# 00_power.net
KiCad netlist of a schematic drawn in Altium Designer
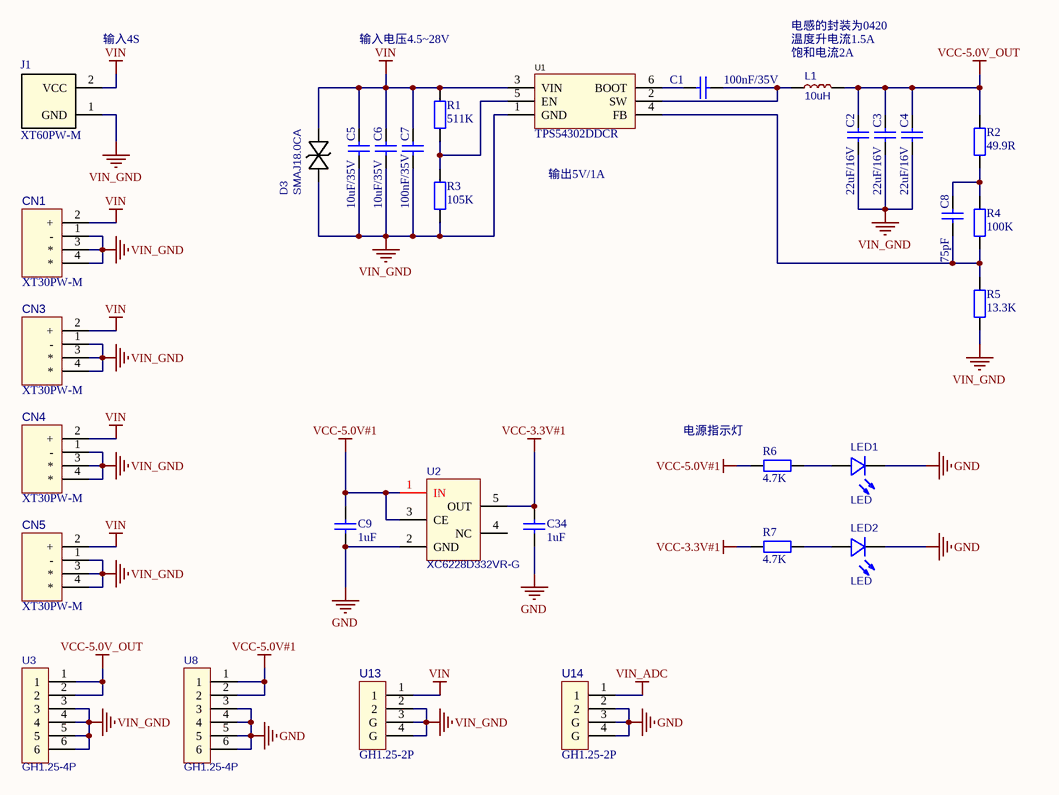
[diagram p0: 00_power.SchDoc]

(export (version "E")
  (design (tool "Eeschema 10.0.6"))
  (components
    (comp (ref "C1")
      (value "100nF/35V")
      (footprint "0603-C")
      (description "贴片电容")
      (libsource (lib "封装库") (part "C"))
    )
    (comp (ref "C2")
      (value "22uF/16V")
      (footprint "1206-C")
      (description "贴片电容")
      (libsource (lib "封装库") (part "C"))
    )
    (comp (ref "C3")
      (value "22uF/16V")
      (footprint "1206-C")
      (description "贴片电容")
      (libsource (lib "封装库") (part "C"))
    )
    (comp (ref "C4")
      (value "22uF/16V")
      (footprint "1206-C")
      (description "贴片电容")
      (libsource (lib "封装库") (part "C"))
    )
    (comp (ref "C5")
      (value "10uF/35V")
      (footprint "0805-C")
      (description "贴片电容")
      (libsource (lib "封装库") (part "C"))
    )
    (comp (ref "C6")
      (value "10uF/35V")
      (footprint "0805-C")
      (description "贴片电容")
      (libsource (lib "封装库") (part "C"))
    )
    (comp (ref "C7")
      (value "100nF/35V")
      (footprint "0805-C")
      (description "贴片电容")
      (libsource (lib "封装库") (part "C"))
    )
    (comp (ref "C8")
      (value "75pF")
      (footprint "0603-C")
      (description "贴片电容")
      (libsource (lib "封装库") (part "C"))
    )
    (comp (ref "C9")
      (value "1uF")
      (footprint "0603-C")
      (description "贴片电容")
      (libsource (lib "封装库") (part "C"))
    )
    (comp (ref "C34")
      (value "1uF")
      (footprint "0603-C")
      (description "贴片电容")
      (libsource (lib "封装库") (part "C"))
    )
    (comp (ref "CN1")
      (value "XT30PW-M")
      (footprint "XT30PW-M")
      (fields (field (name "MANUFACTURER") "AMASS(艾迈斯)"))
      (libsource (lib "封装库") (part "XT30PW-M"))
    )
    (comp (ref "CN3")
      (value "XT30PW-M")
      (footprint "XT30PW-M")
      (fields (field (name "MANUFACTURER") "AMASS(艾迈斯)"))
      (libsource (lib "封装库") (part "XT30PW-M"))
    )
    (comp (ref "CN4")
      (value "XT30PW-M")
      (footprint "XT30PW-M")
      (fields (field (name "MANUFACTURER") "AMASS(艾迈斯)"))
      (libsource (lib "封装库") (part "XT30PW-M"))
    )
    (comp (ref "CN5")
      (value "XT30PW-M")
      (footprint "XT30PW-M")
      (fields (field (name "MANUFACTURER") "AMASS(艾迈斯)"))
      (libsource (lib "封装库") (part "XT30PW-M"))
    )
    (comp (ref "D3")
      (value "SMAJ18.0CA")
      (footprint "ZENER")
      (description "SMAJ6.0CA_C698928")
      (fields
        (field (name "BOM_SUPPLIER PART") "C698928")
        (field (name "BOM_MANUFACTURER PART") "SMAJ6.0CA")
        (field (name "CONTRIBUTOR") "LCSC")
      )
      (libsource (lib "封装库") (part "SMAJ6.0CA"))
    )
    (comp (ref "J1")
      (value "XT60PW-M")
      (footprint "XT60PW-M")
      (description "PCB Power Connector")
      (fields (field (name "MANUFACTURER_PART_NUMBER") "XT60PW-F"))
      (libsource (lib "封装库") (part "XT60PW-M"))
    )
    (comp (ref "L1")
      (value "10uH")
      (footprint "电感 4.2X4.4")
      (description "L")
      (fields
        (field (name "BOM_MANUFACTURER PART") "UPZ2012D800-4R0TF")
        (field (name "BOM_SUPPLIER PART") "C145060")
        (field (name "CONTRIBUTOR") "LCSC")
      )
      (libsource (lib "封装库") (part "L"))
    )
    (comp (ref "LED1")
      (value "LED")
      (footprint "LED-0603")
      (fields
        (field (name "BOM_SUPPLIER PART") "C118334")
        (field (name "BOM_MANUFACTURER PART") "D-G060306G1-KS2")
        (field (name "CONTRIBUTOR") "LCSC")
      )
      (libsource (lib "封装库") (part "LED"))
    )
    (comp (ref "LED2")
      (value "LED")
      (footprint "LED-0603")
      (fields
        (field (name "BOM_SUPPLIER PART") "C118334")
        (field (name "BOM_MANUFACTURER PART") "D-G060306G1-KS2")
        (field (name "CONTRIBUTOR") "LCSC")
      )
      (libsource (lib "封装库") (part "LED"))
    )
    (comp (ref "R1")
      (value "511K")
      (footprint "0603-R")
      (description "贴片电阻")
      (libsource (lib "封装库") (part "R"))
    )
    (comp (ref "R2")
      (value "49.9R")
      (footprint "0603-R")
      (description "贴片电阻")
      (libsource (lib "封装库") (part "R"))
    )
    (comp (ref "R3")
      (value "105K")
      (footprint "0603-R")
      (description "贴片电阻")
      (libsource (lib "封装库") (part "R"))
    )
    (comp (ref "R4")
      (value "100K")
      (footprint "0603-R")
      (description "贴片电阻")
      (libsource (lib "封装库") (part "R"))
    )
    (comp (ref "R5")
      (value "13.3K")
      (footprint "0603-R")
      (description "贴片电阻")
      (libsource (lib "封装库") (part "R"))
    )
    (comp (ref "R6")
      (value "4.7K")
      (footprint "0603-R")
      (description "贴片电阻")
      (libsource (lib "封装库") (part "R"))
    )
    (comp (ref "R7")
      (value "4.7K")
      (footprint "0603-R")
      (description "贴片电阻")
      (libsource (lib "封装库") (part "R"))
    )
    (comp (ref "U1")
      (value "TPS54302DDCR")
      (footprint "TPS54302")
      (fields (field (name "MANUFACTURER") "TI(德州仪器)"))
      (libsource (lib "封装库") (part "TPS54302DDCR"))
    )
    (comp (ref "U2")
      (value "XC6228D332VR-G")
      (footprint "XC6228D332VR-G")
      (fields (field (name "BOM_SUPPLIER PART") "C69841"))
      (libsource (lib "封装库") (part "XC6228D332VR-G"))
    )
    (comp (ref "U3")
      (value "GH1.25-4P")
      (footprint "CONN-SMD_GH1.25-4PWBPZ")
      (description "GH1.25-4PWBPZ")
      (fields (field (name "BOM_SUPPLIER PART") "C2829253") (field (name "CONTRIBUTOR") "LCSC"))
      (libsource (lib "封装库") (part "GH1.25-4P"))
    )
    (comp (ref "U8")
      (value "GH1.25-4P")
      (footprint "CONN-SMD_GH1.25-4PWBPZ")
      (description "GH1.25-4PWBPZ")
      (fields (field (name "BOM_SUPPLIER PART") "C2829253") (field (name "CONTRIBUTOR") "LCSC"))
      (libsource (lib "封装库") (part "GH1.25-4P"))
    )
    (comp (ref "U13")
      (value "GH1.25-2P")
      (footprint "GH1.25-2P")
      (fields (field (name "MANUFACTURER") "Bossie(博锡)") (field (name "MANUFACTURER PART") "BX-GH1.25-2PWT"))
      (libsource (lib "封装库") (part "GH1.25-2P"))
    )
    (comp (ref "U14")
      (value "GH1.25-2P")
      (footprint "GH1.25-2P")
      (fields (field (name "MANUFACTURER") "Bossie(博锡)") (field (name "MANUFACTURER PART") "BX-GH1.25-2PWT"))
      (libsource (lib "封装库") (part "GH1.25-2P"))
    )
  )
  (nets
    (net (code "1") (name "GND") (class "Default")
      (node (ref "C34") (pin "1") (pinfunction "1_1") (pintype "passive"))
      (node (ref "C9") (pin "1") (pinfunction "1_1") (pintype "passive"))
      (node (ref "LED1") (pin "1") (pinfunction "-_1") (pintype "passive"))
      (node (ref "LED2") (pin "1") (pinfunction "-_1") (pintype "passive"))
      (node (ref "U14") (pin "2") (pinfunction "2_2") (pintype "passive"))
      (node (ref "U14") (pin "3") (pinfunction "G_3") (pintype "passive"))
      (node (ref "U14") (pin "4") (pinfunction "G_4") (pintype "passive"))
      (node (ref "U2") (pin "2") (pinfunction "GND_2") (pintype "passive"))
      (node (ref "U8") (pin "3") (pinfunction "3_3") (pintype "passive"))
      (node (ref "U8") (pin "4") (pinfunction "4_4") (pintype "passive"))
      (node (ref "U8") (pin "5") (pinfunction "5_5") (pintype "passive"))
      (node (ref "U8") (pin "6") (pinfunction "6_6") (pintype "passive"))
    )
    (net (code "2") (name "Net-(C8-Pad2)") (class "Default")
      (node (ref "C8") (pin "2") (pinfunction "2_2") (pintype "passive"))
      (node (ref "R2") (pin "1") (pinfunction "1_1") (pintype "passive"))
      (node (ref "R4") (pin "2") (pinfunction "2_2") (pintype "passive"))
    )
    (net (code "3") (name "Net-(LED1-+)") (class "Default")
      (node (ref "LED1") (pin "2") (pinfunction "+_2") (pintype "passive"))
      (node (ref "R6") (pin "2") (pinfunction "2_2") (pintype "passive"))
    )
    (net (code "4") (name "Net-(LED2-+)") (class "Default")
      (node (ref "LED2") (pin "2") (pinfunction "+_2") (pintype "passive"))
      (node (ref "R7") (pin "2") (pinfunction "2_2") (pintype "passive"))
    )
    (net (code "5") (name "Net-(U1-BOOT)") (class "Default")
      (node (ref "C1") (pin "1") (pinfunction "1_1") (pintype "passive"))
      (node (ref "U1") (pin "6") (pinfunction "BOOT_6") (pintype "passive"))
    )
    (net (code "6") (name "Net-(U1-EN)") (class "Default")
      (node (ref "R1") (pin "1") (pinfunction "1_1") (pintype "passive"))
      (node (ref "R3") (pin "2") (pinfunction "2_2") (pintype "passive"))
      (node (ref "U1") (pin "5") (pinfunction "EN_5") (pintype "passive"))
    )
    (net (code "7") (name "Net-(U1-FB)") (class "Default")
      (node (ref "C8") (pin "1") (pinfunction "1_1") (pintype "passive"))
      (node (ref "R4") (pin "1") (pinfunction "1_1") (pintype "passive"))
      (node (ref "R5") (pin "2") (pinfunction "2_2") (pintype "passive"))
      (node (ref "U1") (pin "4") (pinfunction "FB_4") (pintype "passive"))
    )
    (net (code "8") (name "Net-(U1-SW)") (class "Default")
      (node (ref "C1") (pin "2") (pinfunction "2_2") (pintype "passive"))
      (node (ref "L1") (pin "1") (pinfunction "1_1") (pintype "passive"))
      (node (ref "U1") (pin "2") (pinfunction "SW_2") (pintype "passive"))
    )
    (net (code "9") (name "VCC-3.3V#1") (class "Default")
      (node (ref "C34") (pin "2") (pinfunction "2_2") (pintype "passive"))
      (node (ref "R7") (pin "1") (pinfunction "1_1") (pintype "passive"))
      (node (ref "U2") (pin "5") (pinfunction "OUT_5") (pintype "passive"))
    )
    (net (code "10") (name "VCC-5.0V#1") (class "Default")
      (node (ref "C9") (pin "2") (pinfunction "2_2") (pintype "passive"))
      (node (ref "R6") (pin "1") (pinfunction "1_1") (pintype "passive"))
      (node (ref "U2") (pin "1") (pinfunction "IN_1") (pintype "passive"))
      (node (ref "U2") (pin "3") (pinfunction "CE_3") (pintype "passive"))
      (node (ref "U8") (pin "1") (pinfunction "1_1") (pintype "passive"))
      (node (ref "U8") (pin "2") (pinfunction "2_2") (pintype "passive"))
    )
    (net (code "11") (name "VCC-5.0V_OUT") (class "Default")
      (node (ref "C2") (pin "2") (pinfunction "2_2") (pintype "passive"))
      (node (ref "C3") (pin "2") (pinfunction "2_2") (pintype "passive"))
      (node (ref "C4") (pin "2") (pinfunction "2_2") (pintype "passive"))
      (node (ref "L1") (pin "2") (pinfunction "2_2") (pintype "passive"))
      (node (ref "R2") (pin "2") (pinfunction "2_2") (pintype "passive"))
      (node (ref "U3") (pin "1") (pinfunction "1_1") (pintype "passive"))
      (node (ref "U3") (pin "2") (pinfunction "2_2") (pintype "passive"))
    )
    (net (code "12") (name "VIN") (class "Default")
      (node (ref "C5") (pin "2") (pinfunction "2_2") (pintype "passive"))
      (node (ref "C6") (pin "2") (pinfunction "2_2") (pintype "passive"))
      (node (ref "C7") (pin "2") (pinfunction "2_2") (pintype "passive"))
      (node (ref "CN1") (pin "2") (pinfunction "+_2") (pintype "passive"))
      (node (ref "CN3") (pin "2") (pinfunction "+_2") (pintype "passive"))
      (node (ref "CN4") (pin "2") (pinfunction "+_2") (pintype "passive"))
      (node (ref "CN5") (pin "2") (pinfunction "+_2") (pintype "passive"))
      (node (ref "D3") (pin "2") (pinfunction "A_2") (pintype "passive"))
      (node (ref "J1") (pin "2") (pinfunction "VCC_2") (pintype "passive"))
      (node (ref "R1") (pin "2") (pinfunction "2_2") (pintype "passive"))
      (node (ref "U1") (pin "3") (pinfunction "VIN_3") (pintype "passive"))
      (node (ref "U13") (pin "1") (pinfunction "1_1") (pintype "passive"))
    )
    (net (code "13") (name "VIN_ADC") (class "Default")
      (node (ref "U14") (pin "1") (pinfunction "1_1") (pintype "passive"))
    )
    (net (code "14") (name "VIN_GND") (class "Default")
      (node (ref "C2") (pin "1") (pinfunction "1_1") (pintype "passive"))
      (node (ref "C3") (pin "1") (pinfunction "1_1") (pintype "passive"))
      (node (ref "C4") (pin "1") (pinfunction "1_1") (pintype "passive"))
      (node (ref "C5") (pin "1") (pinfunction "1_1") (pintype "passive"))
      (node (ref "C6") (pin "1") (pinfunction "1_1") (pintype "passive"))
      (node (ref "C7") (pin "1") (pinfunction "1_1") (pintype "passive"))
      (node (ref "CN1") (pin "1") (pinfunction "-_1") (pintype "passive"))
      (node (ref "CN1") (pin "3") (pinfunction "*_3") (pintype "passive"))
      (node (ref "CN1") (pin "4") (pinfunction "*_4") (pintype "passive"))
      (node (ref "CN3") (pin "1") (pinfunction "-_1") (pintype "passive"))
      (node (ref "CN3") (pin "3") (pinfunction "*_3") (pintype "passive"))
      (node (ref "CN3") (pin "4") (pinfunction "*_4") (pintype "passive"))
      (node (ref "CN4") (pin "1") (pinfunction "-_1") (pintype "passive"))
      (node (ref "CN4") (pin "3") (pinfunction "*_3") (pintype "passive"))
      (node (ref "CN4") (pin "4") (pinfunction "*_4") (pintype "passive"))
      (node (ref "CN5") (pin "1") (pinfunction "-_1") (pintype "passive"))
      (node (ref "CN5") (pin "3") (pinfunction "*_3") (pintype "passive"))
      (node (ref "CN5") (pin "4") (pinfunction "*_4") (pintype "passive"))
      (node (ref "D3") (pin "1") (pinfunction "C_1") (pintype "passive"))
      (node (ref "J1") (pin "1") (pinfunction "GND_1") (pintype "passive"))
      (node (ref "R3") (pin "1") (pinfunction "1_1") (pintype "passive"))
      (node (ref "R5") (pin "1") (pinfunction "1_1") (pintype "passive"))
      (node (ref "U1") (pin "1") (pinfunction "GND_1") (pintype "passive"))
      (node (ref "U13") (pin "2") (pinfunction "2_2") (pintype "passive"))
      (node (ref "U13") (pin "3") (pinfunction "G_3") (pintype "passive"))
      (node (ref "U13") (pin "4") (pinfunction "G_4") (pintype "passive"))
      (node (ref "U3") (pin "3") (pinfunction "3_3") (pintype "passive"))
      (node (ref "U3") (pin "4") (pinfunction "4_4") (pintype "passive"))
      (node (ref "U3") (pin "5") (pinfunction "5_5") (pintype "passive"))
      (node (ref "U3") (pin "6") (pinfunction "6_6") (pintype "passive"))
    )
    (net (code "15") (name "unconnected-(U2-NC-Pad4)") (class "Default")
      (node (ref "U2") (pin "4") (pinfunction "NC_4") (pintype "passive"))
    )
  )
)
